# Wacky_Racers_87557913.net
KiCad netlist of a schematic drawn in Altium Designer
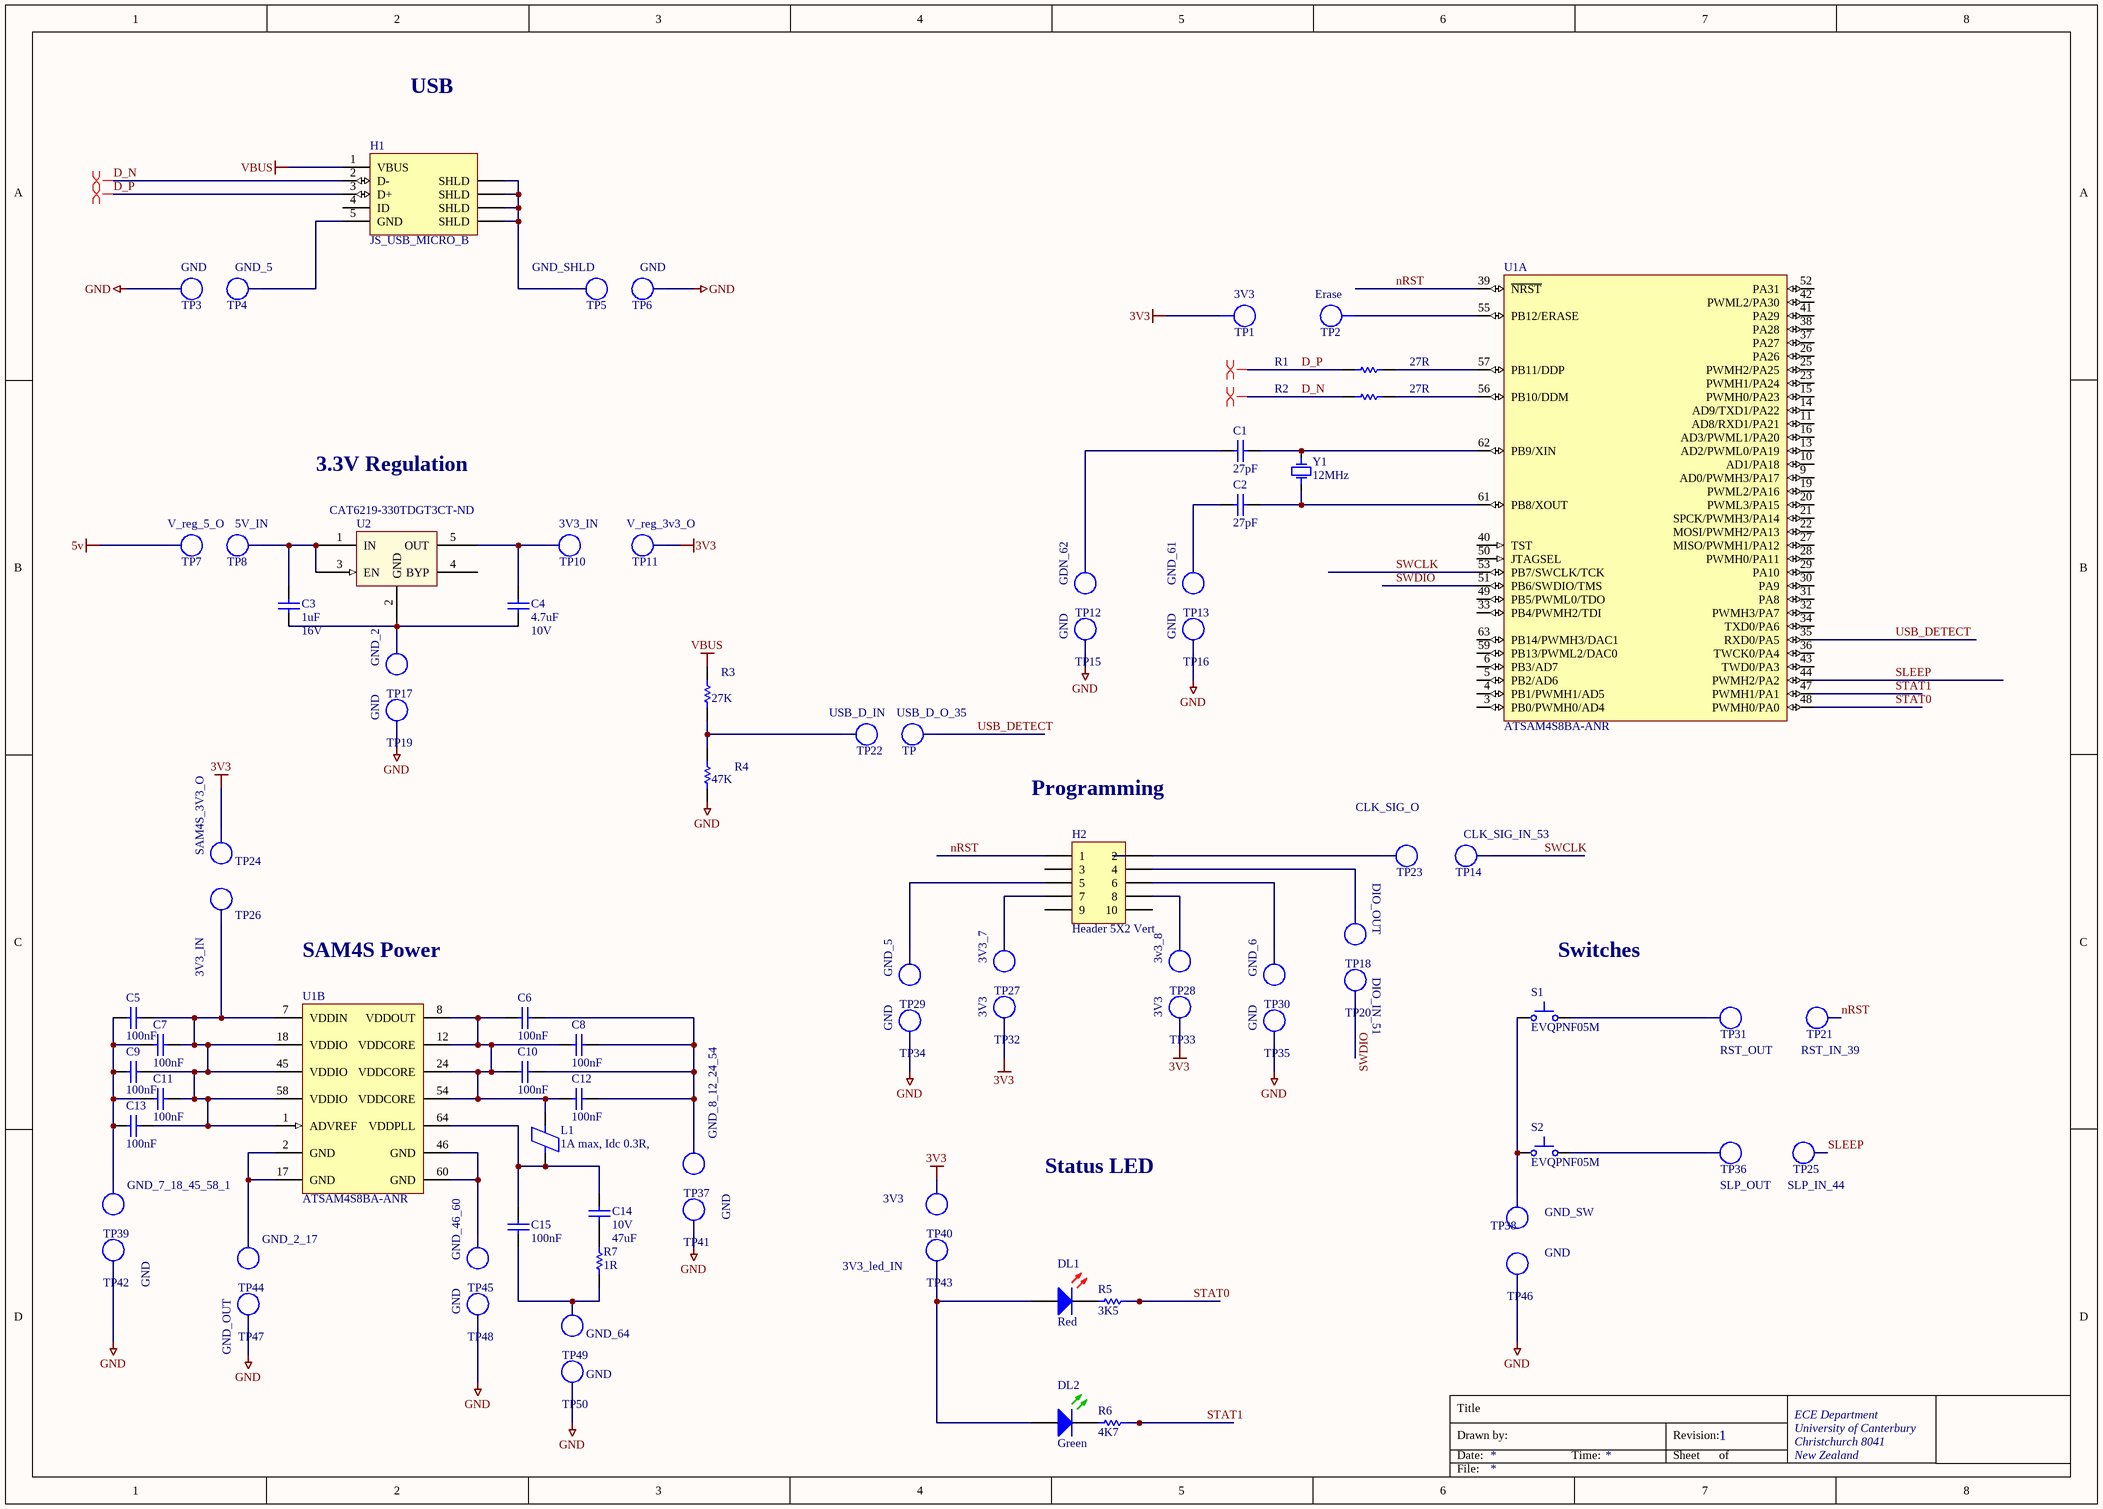
[diagram p0: Wacky_Racers_87557913.SchDoc]

(export (version "E")
  (design (tool "Eeschema 10.0.6"))
  (components
    (comp (ref "C1")
      (value "27pF")
      (footprint "CAPC1608L")
      (description "CAP CER 27pF NPO/COG +-5% 50V 0603")
      (libsource (lib "ECE AD19Components_22V1") (part "CC_27pF_0603"))
    )
    (comp (ref "C2")
      (value "27pF")
      (footprint "CAPC1608L")
      (description "CAP CER 27pF NPO/COG +-5% 50V 0603")
      (libsource (lib "ECE AD19Components_22V1") (part "CC_27pF_0603"))
    )
    (comp (ref "C3")
      (value "1uF")
      (footprint "CAPC1608L")
      (description "CAP CER 1uF Y5V -20% +80% 16V 0603")
      (fields (field (name "MAX VOLTAGE") "16V"))
      (libsource (lib "ECE AD19Components_22V1") (part "CC_1uF_0603"))
    )
    (comp (ref "C4")
      (value "4.7uF")
      (footprint "CAPC1608N")
      (description "CAP CER 4.7uF X5R +-20%  10V 0603")
      (fields (field (name "MAX VOLTAGE") "10V"))
      (libsource (lib "ECE AD19Components_22V1") (part "CC_4.7uF_0603"))
    )
    (comp (ref "C5")
      (value "100nF")
      (footprint "CAPC1608L")
      (description "CAP CER 100nF X7R +-10% 50V 0603")
      (libsource (lib "ECE AD19Components_22V1") (part "CC_100nF_0603"))
    )
    (comp (ref "C6")
      (value "100nF")
      (footprint "CAPC1608L")
      (description "CAP CER 100nF X7R +-10% 50V 0603")
      (libsource (lib "ECE AD19Components_22V1") (part "CC_100nF_0603"))
    )
    (comp (ref "C7")
      (value "100nF")
      (footprint "CAPC1608L")
      (description "CAP CER 100nF X7R +-10% 50V 0603")
      (libsource (lib "ECE AD19Components_22V1") (part "CC_100nF_0603"))
    )
    (comp (ref "C8")
      (value "100nF")
      (footprint "CAPC1608L")
      (description "CAP CER 100nF X7R +-10% 50V 0603")
      (libsource (lib "ECE AD19Components_22V1") (part "CC_100nF_0603"))
    )
    (comp (ref "C9")
      (value "100nF")
      (footprint "CAPC1608L")
      (description "CAP CER 100nF X7R +-10% 50V 0603")
      (libsource (lib "ECE AD19Components_22V1") (part "CC_100nF_0603"))
    )
    (comp (ref "C10")
      (value "100nF")
      (footprint "CAPC1608L")
      (description "CAP CER 100nF X7R +-10% 50V 0603")
      (libsource (lib "ECE AD19Components_22V1") (part "CC_100nF_0603"))
    )
    (comp (ref "C11")
      (value "100nF")
      (footprint "CAPC1608L")
      (description "CAP CER 100nF X7R +-10% 50V 0603")
      (libsource (lib "ECE AD19Components_22V1") (part "CC_100nF_0603"))
    )
    (comp (ref "C12")
      (value "100nF")
      (footprint "CAPC1608L")
      (description "CAP CER 100nF X7R +-10% 50V 0603")
      (libsource (lib "ECE AD19Components_22V1") (part "CC_100nF_0603"))
    )
    (comp (ref "C13")
      (value "100nF")
      (footprint "CAPC1608L")
      (description "CAP CER 100nF X7R +-10% 50V 0603")
      (libsource (lib "ECE AD19Components_22V1") (part "CC_100nF_0603"))
    )
    (comp (ref "C14")
      (value "47uF")
      (footprint "CAPC3216L")
      (description "CAP CER 47uF X5R -/+20% 10V 1206")
      (fields (field (name "MAX VOLTAGE") "10V"))
      (libsource (lib "ECE AD19Components_22V1") (part "CC_47uF_1206"))
    )
    (comp (ref "C15")
      (value "100nF")
      (footprint "CAPC1608L")
      (description "CAP CER 100nF X7R +-10% 50V 0603")
      (libsource (lib "ECE AD19Components_22V1") (part "CC_100nF_0603"))
    )
    (comp (ref "DL1")
      (value "Red")
      (footprint "WL-SMCW0603")
      (description "LED Red 250mcd 0603 SMD")
      (fields
        (field (name "MANUFACTURER") "WURTH ELEKTRONIK")
        (field (name "MANUFACTURER PART NUMBER") "150060RS75000")
        (field (name "LED COLOUR") "Red")
      )
      (libsource (lib "ECE AD19Components_22V1") (part "DL_150060RS75000"))
    )
    (comp (ref "DL2")
      (value "Green")
      (footprint "WL-SMCW0603")
      (description "LED Green 430mcd 0603 SMD")
      (fields
        (field (name "MANUFACTURER") "WURTH ELEKTRONIK")
        (field (name "MANUFACTURER PART NUMBER") "150060GS75000")
        (field (name "LED COLOUR") "Green")
      )
      (libsource (lib "ECE AD19Components_22V1") (part "DL_150060GS75000"))
    )
    (comp (ref "H1")
      (value "JS_USB_MICRO_B")
      (footprint "FCI_USB_10118194-0001LF")
      (description "CONN USB MICRO B RECPT SMT R/A")
      (fields (field (name "MANUFACTURER") "FCI") (field (name "MANUFACTURER PART NUMBER") "10118194-0001LF"))
      (libsource (lib "ECE AD19Components_22V1") (part "JS_USB_MICRO_B_SMT"))
    )
    (comp (ref "H2")
      (value "Header 5X2 Vert")
      (footprint "IDC2.54-V10D")
      (description "IDC Header, 2,54mm, 10-Pin, Vert")
      (libsource (lib "ECE AD19Components_22V1") (part "JA_HDR_IDC_5X2_VERT"))
    )
    (comp (ref "L1")
      (value "1A max, Idc 0.3R,")
      (footprint "INDC3216L")
      (description "Ferrite Bead, Rdc 0.3R, Z100MHZ 600R, Imax 1A, SMD 1206")
      (fields
        (field (name "MANUFACTURER") "FAIR-RITE")
        (field (name "MANUFACTURER PART NUMBER") "2512066017Y1")
      )
      (libsource (lib "ECE AD19Components_22V1") (part "IN_Ferrite-Bead"))
    )
    (comp (ref "R1")
      (value "27R")
      (footprint "RESC1608L")
      (description "RES 27 OHM 1/10W 5% 0603 SMD")
      (libsource (lib "ECE AD19Components_22V1") (part "RS_27R"))
    )
    (comp (ref "R2")
      (value "27R")
      (footprint "RESC1608L")
      (description "RES 27 OHM 1/10W 5% 0603 SMD")
      (libsource (lib "ECE AD19Components_22V1") (part "RS_27R"))
    )
    (comp (ref "R3")
      (value "27K")
      (footprint "RESC1608L")
      (description "RES 27K OHM 1/10W 5% 0603 SMD")
      (libsource (lib "ECE AD19Components_22V1") (part "RS_27K"))
    )
    (comp (ref "R4")
      (value "47K")
      (footprint "RESC1608N")
      (description "RES 47.0K OHM 1/10W 5% 0603 SMD")
      (libsource (lib "ECE AD19Components_22V1") (part "RS_47K"))
    )
    (comp (ref "R5")
      (value "3K5")
      (footprint "RESC1608L")
      (description "RES 4.7K OHM 1/10W 5% 0603 SMD")
      (libsource (lib "ECE AD19Components_22V1") (part "RS_4K7"))
    )
    (comp (ref "R6")
      (value "4K7")
      (footprint "RESC1608L")
      (description "RES 4.7K OHM 1/10W 5% 0603 SMD")
      (libsource (lib "ECE AD19Components_22V1") (part "RS_4K7"))
    )
    (comp (ref "R7")
      (value "1R")
      (footprint "RESC3216L")
      (description "RES 1R OHM 1/4W 5% 1206 SMD")
      (libsource (lib "ECE AD19Components_22V1") (part "RT_1R"))
    )
    (comp (ref "S1")
      (value "EVQPNF05M")
      (footprint "EVQPNF05M")
      (description "Panasonic 6 x 3.5mm SMD Light Touch Switch Type SMD")
      (fields (field (name "MANUFACTURER") "Panasonic"))
      (libsource (lib "ECE AD19Components_22V1") (part "WS_EVQPNF05M"))
    )
    (comp (ref "S2")
      (value "EVQPNF05M")
      (footprint "EVQPNF05M")
      (description "Panasonic 6 x 3.5mm SMD Light Touch Switch Type SMD")
      (fields (field (name "MANUFACTURER") "Panasonic"))
      (libsource (lib "ECE AD19Components_22V1") (part "WS_EVQPNF05M"))
    )
    (comp (ref "TP")
      (value "TP_0603")
      (footprint "TP_0603")
      (description "Test Point 1.65X0.9X1.2mm SMD")
      (fields
        (field (name "MANUFACTURER") "TE Connectivity AMP Connectors")
        (field (name "MANUFACTURER PART NUMBER") "1625854-3")
      )
      (libsource (lib "ECE AD19Components_22V1") (part "TP_0603"))
    )
    (comp (ref "TP1")
      (value "TP")
      (footprint "TP_1206")
      (description "Test-Point 3.3x1.6x2.1mm SMD")
      (fields
        (field (name "MANUFACTURER") "Harwin Inc")
        (field (name "MANUFACTURER PART NUMBER") "S1751-46R")
      )
      (libsource (lib "ECE AD19Components_22V1") (part "TP_1206"))
    )
    (comp (ref "TP2")
      (value "TP")
      (footprint "TP_1206")
      (description "Test-Point 3.3x1.6x2.1mm SMD")
      (fields
        (field (name "MANUFACTURER") "Harwin Inc")
        (field (name "MANUFACTURER PART NUMBER") "S1751-46R")
      )
      (libsource (lib "ECE AD19Components_22V1") (part "TP_1206"))
    )
    (comp (ref "TP3")
      (value "TP_0603")
      (footprint "TP_0603")
      (description "Test Point 1.65X0.9X1.2mm SMD")
      (fields
        (field (name "MANUFACTURER") "TE Connectivity AMP Connectors")
        (field (name "MANUFACTURER PART NUMBER") "1625854-3")
      )
      (libsource (lib "ECE AD19Components_22V1") (part "TP_0603"))
    )
    (comp (ref "TP4")
      (value "TP_0603")
      (footprint "TP_0603")
      (description "Test Point 1.65X0.9X1.2mm SMD")
      (fields
        (field (name "MANUFACTURER") "TE Connectivity AMP Connectors")
        (field (name "MANUFACTURER PART NUMBER") "1625854-3")
      )
      (libsource (lib "ECE AD19Components_22V1") (part "TP_0603"))
    )
    (comp (ref "TP5")
      (value "TP_0603")
      (footprint "TP_0603")
      (description "Test Point 1.65X0.9X1.2mm SMD")
      (fields
        (field (name "MANUFACTURER") "TE Connectivity AMP Connectors")
        (field (name "MANUFACTURER PART NUMBER") "1625854-3")
      )
      (libsource (lib "ECE AD19Components_22V1") (part "TP_0603"))
    )
    (comp (ref "TP6")
      (value "TP_0603")
      (footprint "TP_0603")
      (description "Test Point 1.65X0.9X1.2mm SMD")
      (fields
        (field (name "MANUFACTURER") "TE Connectivity AMP Connectors")
        (field (name "MANUFACTURER PART NUMBER") "1625854-3")
      )
      (libsource (lib "ECE AD19Components_22V1") (part "TP_0603"))
    )
    (comp (ref "TP7")
      (value "TP_0603")
      (footprint "TP_0603")
      (description "Test Point 1.65X0.9X1.2mm SMD")
      (fields
        (field (name "MANUFACTURER") "TE Connectivity AMP Connectors")
        (field (name "MANUFACTURER PART NUMBER") "1625854-3")
      )
      (libsource (lib "ECE AD19Components_22V1") (part "TP_0603"))
    )
    (comp (ref "TP8")
      (value "TP_0603")
      (footprint "TP_0603")
      (description "Test Point 1.65X0.9X1.2mm SMD")
      (fields
        (field (name "MANUFACTURER") "TE Connectivity AMP Connectors")
        (field (name "MANUFACTURER PART NUMBER") "1625854-3")
      )
      (libsource (lib "ECE AD19Components_22V1") (part "TP_0603"))
    )
    (comp (ref "TP10")
      (value "TP_0603")
      (footprint "TP_0603")
      (description "Test Point 1.65X0.9X1.2mm SMD")
      (fields
        (field (name "MANUFACTURER") "TE Connectivity AMP Connectors")
        (field (name "MANUFACTURER PART NUMBER") "1625854-3")
      )
      (libsource (lib "ECE AD19Components_22V1") (part "TP_0603"))
    )
    (comp (ref "TP11")
      (value "TP_0603")
      (footprint "TP_0603")
      (description "Test Point 1.65X0.9X1.2mm SMD")
      (fields
        (field (name "MANUFACTURER") "TE Connectivity AMP Connectors")
        (field (name "MANUFACTURER PART NUMBER") "1625854-3")
      )
      (libsource (lib "ECE AD19Components_22V1") (part "TP_0603"))
    )
    (comp (ref "TP12")
      (value "TP_0603")
      (footprint "TP_0603")
      (description "Test Point 1.65X0.9X1.2mm SMD")
      (fields
        (field (name "MANUFACTURER") "TE Connectivity AMP Connectors")
        (field (name "MANUFACTURER PART NUMBER") "1625854-3")
      )
      (libsource (lib "ECE AD19Components_22V1") (part "TP_0603"))
    )
    (comp (ref "TP13")
      (value "TP_0603")
      (footprint "TP_0603")
      (description "Test Point 1.65X0.9X1.2mm SMD")
      (fields
        (field (name "MANUFACTURER") "TE Connectivity AMP Connectors")
        (field (name "MANUFACTURER PART NUMBER") "1625854-3")
      )
      (libsource (lib "ECE AD19Components_22V1") (part "TP_0603"))
    )
    (comp (ref "TP14")
      (value "TP_0603")
      (footprint "TP_0603")
      (description "Test Point 1.65X0.9X1.2mm SMD")
      (fields
        (field (name "MANUFACTURER") "TE Connectivity AMP Connectors")
        (field (name "MANUFACTURER PART NUMBER") "1625854-3")
      )
      (libsource (lib "ECE AD19Components_22V1") (part "TP_0603"))
    )
    (comp (ref "TP15")
      (value "TP_0603")
      (footprint "TP_0603")
      (description "Test Point 1.65X0.9X1.2mm SMD")
      (fields
        (field (name "MANUFACTURER") "TE Connectivity AMP Connectors")
        (field (name "MANUFACTURER PART NUMBER") "1625854-3")
      )
      (libsource (lib "ECE AD19Components_22V1") (part "TP_0603"))
    )
    (comp (ref "TP16")
      (value "TP_0603")
      (footprint "TP_0603")
      (description "Test Point 1.65X0.9X1.2mm SMD")
      (fields
        (field (name "MANUFACTURER") "TE Connectivity AMP Connectors")
        (field (name "MANUFACTURER PART NUMBER") "1625854-3")
      )
      (libsource (lib "ECE AD19Components_22V1") (part "TP_0603"))
    )
    (comp (ref "TP17")
      (value "TP_0603")
      (footprint "TP_0603")
      (description "Test Point 1.65X0.9X1.2mm SMD")
      (fields
        (field (name "MANUFACTURER") "TE Connectivity AMP Connectors")
        (field (name "MANUFACTURER PART NUMBER") "1625854-3")
      )
      (libsource (lib "ECE AD19Components_22V1") (part "TP_0603"))
    )
    (comp (ref "TP18")
      (value "TP_0603")
      (footprint "TP_0603")
      (description "Test Point 1.65X0.9X1.2mm SMD")
      (fields
        (field (name "MANUFACTURER") "TE Connectivity AMP Connectors")
        (field (name "MANUFACTURER PART NUMBER") "1625854-3")
      )
      (libsource (lib "ECE AD19Components_22V1") (part "TP_0603"))
    )
    (comp (ref "TP19")
      (value "TP_0603")
      (footprint "TP_0603")
      (description "Test Point 1.65X0.9X1.2mm SMD")
      (fields
        (field (name "MANUFACTURER") "TE Connectivity AMP Connectors")
        (field (name "MANUFACTURER PART NUMBER") "1625854-3")
      )
      (libsource (lib "ECE AD19Components_22V1") (part "TP_0603"))
    )
    (comp (ref "TP20")
      (value "TP_0603")
      (footprint "TP_0603")
      (description "Test Point 1.65X0.9X1.2mm SMD")
      (fields
        (field (name "MANUFACTURER") "TE Connectivity AMP Connectors")
        (field (name "MANUFACTURER PART NUMBER") "1625854-3")
      )
      (libsource (lib "ECE AD19Components_22V1") (part "TP_0603"))
    )
    (comp (ref "TP21")
      (value "TP_0603")
      (footprint "TP_0603")
      (description "Test Point 1.65X0.9X1.2mm SMD")
      (fields
        (field (name "MANUFACTURER") "TE Connectivity AMP Connectors")
        (field (name "MANUFACTURER PART NUMBER") "1625854-3")
      )
      (libsource (lib "ECE AD19Components_22V1") (part "TP_0603"))
    )
    (comp (ref "TP22")
      (value "TP_0603")
      (footprint "TP_0603")
      (description "Test Point 1.65X0.9X1.2mm SMD")
      (fields
        (field (name "MANUFACTURER") "TE Connectivity AMP Connectors")
        (field (name "MANUFACTURER PART NUMBER") "1625854-3")
      )
      (libsource (lib "ECE AD19Components_22V1") (part "TP_0603"))
    )
    (comp (ref "TP23")
      (value "TP_0603")
      (footprint "TP_0603")
      (description "Test Point 1.65X0.9X1.2mm SMD")
      (fields
        (field (name "MANUFACTURER") "TE Connectivity AMP Connectors")
        (field (name "MANUFACTURER PART NUMBER") "1625854-3")
      )
      (libsource (lib "ECE AD19Components_22V1") (part "TP_0603"))
    )
    (comp (ref "TP24")
      (value "TP_0603")
      (footprint "TP_0603")
      (description "Test Point 1.65X0.9X1.2mm SMD")
      (fields
        (field (name "MANUFACTURER") "TE Connectivity AMP Connectors")
        (field (name "MANUFACTURER PART NUMBER") "1625854-3")
      )
      (libsource (lib "ECE AD19Components_22V1") (part "TP_0603"))
    )
    (comp (ref "TP25")
      (value "TP_0603")
      (footprint "TP_0603")
      (description "Test Point 1.65X0.9X1.2mm SMD")
      (fields
        (field (name "MANUFACTURER") "TE Connectivity AMP Connectors")
        (field (name "MANUFACTURER PART NUMBER") "1625854-3")
      )
      (libsource (lib "ECE AD19Components_22V1") (part "TP_0603"))
    )
    (comp (ref "TP26")
      (value "TP_0603")
      (footprint "TP_0603")
      (description "Test Point 1.65X0.9X1.2mm SMD")
      (fields
        (field (name "MANUFACTURER") "TE Connectivity AMP Connectors")
        (field (name "MANUFACTURER PART NUMBER") "1625854-3")
      )
      (libsource (lib "ECE AD19Components_22V1") (part "TP_0603"))
    )
    (comp (ref "TP27")
      (value "TP_0603")
      (footprint "TP_0603")
      (description "Test Point 1.65X0.9X1.2mm SMD")
      (fields
        (field (name "MANUFACTURER") "TE Connectivity AMP Connectors")
        (field (name "MANUFACTURER PART NUMBER") "1625854-3")
      )
      (libsource (lib "ECE AD19Components_22V1") (part "TP_0603"))
    )
    (comp (ref "TP28")
      (value "TP_0603")
      (footprint "TP_0603")
      (description "Test Point 1.65X0.9X1.2mm SMD")
      (fields
        (field (name "MANUFACTURER") "TE Connectivity AMP Connectors")
        (field (name "MANUFACTURER PART NUMBER") "1625854-3")
      )
      (libsource (lib "ECE AD19Components_22V1") (part "TP_0603"))
    )
    (comp (ref "TP29")
      (value "TP_0603")
      (footprint "TP_0603")
      (description "Test Point 1.65X0.9X1.2mm SMD")
      (fields
        (field (name "MANUFACTURER") "TE Connectivity AMP Connectors")
        (field (name "MANUFACTURER PART NUMBER") "1625854-3")
      )
      (libsource (lib "ECE AD19Components_22V1") (part "TP_0603"))
    )
    (comp (ref "TP30")
      (value "TP_0603")
      (footprint "TP_0603")
      (description "Test Point 1.65X0.9X1.2mm SMD")
      (fields
        (field (name "MANUFACTURER") "TE Connectivity AMP Connectors")
        (field (name "MANUFACTURER PART NUMBER") "1625854-3")
      )
      (libsource (lib "ECE AD19Components_22V1") (part "TP_0603"))
    )
    (comp (ref "TP31")
      (value "TP_0603")
      (footprint "TP_0603")
      (description "Test Point 1.65X0.9X1.2mm SMD")
      (fields
        (field (name "MANUFACTURER") "TE Connectivity AMP Connectors")
        (field (name "MANUFACTURER PART NUMBER") "1625854-3")
      )
      (libsource (lib "ECE AD19Components_22V1") (part "TP_0603"))
    )
    (comp (ref "TP32")
      (value "TP_0603")
      (footprint "TP_0603")
      (description "Test Point 1.65X0.9X1.2mm SMD")
      (fields
        (field (name "MANUFACTURER") "TE Connectivity AMP Connectors")
        (field (name "MANUFACTURER PART NUMBER") "1625854-3")
      )
      (libsource (lib "ECE AD19Components_22V1") (part "TP_0603"))
    )
    (comp (ref "TP33")
      (value "TP_0603")
      (footprint "TP_0603")
      (description "Test Point 1.65X0.9X1.2mm SMD")
      (fields
        (field (name "MANUFACTURER") "TE Connectivity AMP Connectors")
        (field (name "MANUFACTURER PART NUMBER") "1625854-3")
      )
      (libsource (lib "ECE AD19Components_22V1") (part "TP_0603"))
    )
    (comp (ref "TP34")
      (value "TP_0603")
      (footprint "TP_0603")
      (description "Test Point 1.65X0.9X1.2mm SMD")
      (fields
        (field (name "MANUFACTURER") "TE Connectivity AMP Connectors")
        (field (name "MANUFACTURER PART NUMBER") "1625854-3")
      )
      (libsource (lib "ECE AD19Components_22V1") (part "TP_0603"))
    )
    (comp (ref "TP35")
      (value "TP_0603")
      (footprint "TP_0603")
      (description "Test Point 1.65X0.9X1.2mm SMD")
      (fields
        (field (name "MANUFACTURER") "TE Connectivity AMP Connectors")
        (field (name "MANUFACTURER PART NUMBER") "1625854-3")
      )
      (libsource (lib "ECE AD19Components_22V1") (part "TP_0603"))
    )
    (comp (ref "TP36")
      (value "TP_0603")
      (footprint "TP_0603")
      (description "Test Point 1.65X0.9X1.2mm SMD")
      (fields
        (field (name "MANUFACTURER") "TE Connectivity AMP Connectors")
        (field (name "MANUFACTURER PART NUMBER") "1625854-3")
      )
      (libsource (lib "ECE AD19Components_22V1") (part "TP_0603"))
    )
    (comp (ref "TP37")
      (value "TP_0603")
      (footprint "TP_0603")
      (description "Test Point 1.65X0.9X1.2mm SMD")
      (fields
        (field (name "MANUFACTURER") "TE Connectivity AMP Connectors")
        (field (name "MANUFACTURER PART NUMBER") "1625854-3")
      )
      (libsource (lib "ECE AD19Components_22V1") (part "TP_0603"))
    )
    (comp (ref "TP38")
      (value "TP_0603")
      (footprint "TP_0603")
      (description "Test Point 1.65X0.9X1.2mm SMD")
      (fields
        (field (name "MANUFACTURER") "TE Connectivity AMP Connectors")
        (field (name "MANUFACTURER PART NUMBER") "1625854-3")
      )
      (libsource (lib "ECE AD19Components_22V1") (part "TP_0603"))
    )
    (comp (ref "TP39")
      (value "TP_0603")
      (footprint "TP_0603")
      (description "Test Point 1.65X0.9X1.2mm SMD")
      (fields
        (field (name "MANUFACTURER") "TE Connectivity AMP Connectors")
        (field (name "MANUFACTURER PART NUMBER") "1625854-3")
      )
      (libsource (lib "ECE AD19Components_22V1") (part "TP_0603"))
    )
    (comp (ref "TP40")
      (value "TP_0603")
      (footprint "TP_0603")
      (description "Test Point 1.65X0.9X1.2mm SMD")
      (fields
        (field (name "MANUFACTURER") "TE Connectivity AMP Connectors")
        (field (name "MANUFACTURER PART NUMBER") "1625854-3")
      )
      (libsource (lib "ECE AD19Components_22V1") (part "TP_0603"))
    )
    (comp (ref "TP41")
      (value "TP_0603")
      (footprint "TP_0603")
      (description "Test Point 1.65X0.9X1.2mm SMD")
      (fields
        (field (name "MANUFACTURER") "TE Connectivity AMP Connectors")
        (field (name "MANUFACTURER PART NUMBER") "1625854-3")
      )
      (libsource (lib "ECE AD19Components_22V1") (part "TP_0603"))
    )
    (comp (ref "TP42")
      (value "TP_0603")
      (footprint "TP_0603")
      (description "Test Point 1.65X0.9X1.2mm SMD")
      (fields
        (field (name "MANUFACTURER") "TE Connectivity AMP Connectors")
        (field (name "MANUFACTURER PART NUMBER") "1625854-3")
      )
      (libsource (lib "ECE AD19Components_22V1") (part "TP_0603"))
    )
    (comp (ref "TP43")
      (value "TP_0603")
      (footprint "TP_0603")
      (description "Test Point 1.65X0.9X1.2mm SMD")
      (fields
        (field (name "MANUFACTURER") "TE Connectivity AMP Connectors")
        (field (name "MANUFACTURER PART NUMBER") "1625854-3")
      )
      (libsource (lib "ECE AD19Components_22V1") (part "TP_0603"))
    )
    (comp (ref "TP44")
      (value "TP_0603")
      (footprint "TP_0603")
      (description "Test Point 1.65X0.9X1.2mm SMD")
      (fields
        (field (name "MANUFACTURER") "TE Connectivity AMP Connectors")
        (field (name "MANUFACTURER PART NUMBER") "1625854-3")
      )
      (libsource (lib "ECE AD19Components_22V1") (part "TP_0603"))
    )
    (comp (ref "TP45")
      (value "TP_0603")
      (footprint "TP_0603")
      (description "Test Point 1.65X0.9X1.2mm SMD")
      (fields
        (field (name "MANUFACTURER") "TE Connectivity AMP Connectors")
        (field (name "MANUFACTURER PART NUMBER") "1625854-3")
      )
      (libsource (lib "ECE AD19Components_22V1") (part "TP_0603"))
    )
    (comp (ref "TP46")
      (value "TP_0603")
      (footprint "TP_0603")
      (description "Test Point 1.65X0.9X1.2mm SMD")
      (fields
        (field (name "MANUFACTURER") "TE Connectivity AMP Connectors")
        (field (name "MANUFACTURER PART NUMBER") "1625854-3")
      )
      (libsource (lib "ECE AD19Components_22V1") (part "TP_0603"))
    )
    (comp (ref "TP47")
      (value "TP_0603")
      (footprint "TP_0603")
      (description "Test Point 1.65X0.9X1.2mm SMD")
      (fields
        (field (name "MANUFACTURER") "TE Connectivity AMP Connectors")
        (field (name "MANUFACTURER PART NUMBER") "1625854-3")
      )
      (libsource (lib "ECE AD19Components_22V1") (part "TP_0603"))
    )
    (comp (ref "TP48")
      (value "TP_0603")
      (footprint "TP_0603")
      (description "Test Point 1.65X0.9X1.2mm SMD")
      (fields
        (field (name "MANUFACTURER") "TE Connectivity AMP Connectors")
        (field (name "MANUFACTURER PART NUMBER") "1625854-3")
      )
      (libsource (lib "ECE AD19Components_22V1") (part "TP_0603"))
    )
    (comp (ref "TP49")
      (value "TP_0603")
      (footprint "TP_0603")
      (description "Test Point 1.65X0.9X1.2mm SMD")
      (fields
        (field (name "MANUFACTURER") "TE Connectivity AMP Connectors")
        (field (name "MANUFACTURER PART NUMBER") "1625854-3")
      )
      (libsource (lib "ECE AD19Components_22V1") (part "TP_0603"))
    )
    (comp (ref "TP50")
      (value "TP_0603")
      (footprint "TP_0603")
      (description "Test Point 1.65X0.9X1.2mm SMD")
      (fields
        (field (name "MANUFACTURER") "TE Connectivity AMP Connectors")
        (field (name "MANUFACTURER PART NUMBER") "1625854-3")
      )
      (libsource (lib "ECE AD19Components_22V1") (part "TP_0603"))
    )
    (comp (ref "U1")
      (value "ATSAM4S8BA-ANR")
      (footprint "LQFP64_L")
      (description "IC MCU 32BIT 512KB FLASH 64LQFP")
      (fields (field (name "MANUFACTURER") "Atmel"))
      (libsource (lib "ECE AD19Components_22V1") (part "SE_ATSAM4S16BA-MU"))
    )
    (comp (ref "U2")
      (value "CAT6219-330TDGT3")
      (footprint "SOT95P280X145-5N")
      (description "IC REG LIN 3.3V 500MA TSOT23-5")
      (fields
        (field (name "BASE PART NUMBER") "CAT6219")
        (field (name "SUPPLIER PART NUMBER") "CAT6219-330TDGT3CT-ND")
      )
      (libsource (lib "ENCE461AD19_V23") (part "SV_CAT6219-330TDGT3"))
    )
    (comp (ref "Y1")
      (value "12MHz")
      (footprint "6.0X3.5-4")
      (description "CRYSTAL 12MHZ 18PF 6X3.5mm SMD")
      (fields
        (field (name "MANUFACTURER") "CTS-Frequency Controls")
        (field (name "MANUFACTURER PART NUMBER") "406C35D12M00000")
        (field (name "FREQUENCY") "12MHz")
      )
      (libsource (lib "ECE AD19Components_22V1") (part "XT_CRYSTAL_12MHz_18pF"))
    )
  )
  (nets
    (net (code "1") (name "/D_N") (class "Default")
      (node (ref "H1") (pin "2") (pinfunction "D-_2") (pintype "bidirectional"))
      (node (ref "R2") (pin "1") (pinfunction "1_1") (pintype "passive"))
    )
    (net (code "2") (name "/D_P") (class "Default")
      (node (ref "H1") (pin "3") (pinfunction "D+_3") (pintype "bidirectional"))
      (node (ref "R1") (pin "1") (pinfunction "1_1") (pintype "passive"))
    )
    (net (code "3") (name "/SLEEP") (class "Default")
      (node (ref "TP25") (pin "1") (pinfunction "TP_1") (pintype "passive"))
      (node (ref "U1") (pin "44") (pinfunction "PWMH2/PA2_44") (pintype "bidirectional"))
    )
    (net (code "4") (name "/STAT0") (class "Default")
      (node (ref "R5") (pin "2") (pinfunction "2_2") (pintype "passive"))
      (node (ref "U1") (pin "48") (pinfunction "PWMH0/PA0_48") (pintype "bidirectional"))
    )
    (net (code "5") (name "/STAT1") (class "Default")
      (node (ref "R6") (pin "2") (pinfunction "2_2") (pintype "passive"))
      (node (ref "U1") (pin "47") (pinfunction "PWMH1/PA1_47") (pintype "bidirectional"))
    )
    (net (code "6") (name "/SWCLK") (class "Default")
      (node (ref "TP14") (pin "1") (pinfunction "TP_1") (pintype "passive"))
      (node (ref "U1") (pin "53") (pinfunction "PB7/SWCLK/TCK_53") (pintype "bidirectional"))
    )
    (net (code "7") (name "/SWDIO") (class "Default")
      (node (ref "TP20") (pin "1") (pinfunction "TP_1") (pintype "passive"))
      (node (ref "U1") (pin "51") (pinfunction "PB6/SWDIO/TMS_51") (pintype "bidirectional"))
    )
    (net (code "8") (name "/USB_DETECT") (class "Default")
      (node (ref "TP") (pin "1") (pinfunction "TP_1") (pintype "passive"))
      (node (ref "U1") (pin "35") (pinfunction "RXD0/PA5_35") (pintype "bidirectional"))
    )
    (net (code "9") (name "/nRST") (class "Default")
      (node (ref "H2") (pin "1") (pinfunction "1_1") (pintype "passive"))
      (node (ref "TP21") (pin "1") (pinfunction "TP_1") (pintype "passive"))
      (node (ref "U1") (pin "39") (pinfunction "~{NRST}_39") (pintype "bidirectional"))
    )
    (net (code "10") (name "3V3") (class "Default")
      (node (ref "TP1") (pin "1") (pinfunction "1_1") (pintype "passive"))
      (node (ref "TP11") (pin "1") (pinfunction "TP_1") (pintype "passive"))
      (node (ref "TP24") (pin "1") (pinfunction "TP_1") (pintype "passive"))
      (node (ref "TP32") (pin "1") (pinfunction "TP_1") (pintype "passive"))
      (node (ref "TP33") (pin "1") (pinfunction "TP_1") (pintype "passive"))
      (node (ref "TP40") (pin "1") (pinfunction "TP_1") (pintype "passive"))
    )
    (net (code "11") (name "5v") (class "Default")
      (node (ref "TP7") (pin "1") (pinfunction "TP_1") (pintype "passive"))
    )
    (net (code "12") (name "GND") (class "Default")
      (node (ref "R4") (pin "1") (pinfunction "1_1") (pintype "passive"))
      (node (ref "TP15") (pin "1") (pinfunction "TP_1") (pintype "passive"))
      (node (ref "TP16") (pin "1") (pinfunction "TP_1") (pintype "passive"))
      (node (ref "TP19") (pin "1") (pinfunction "TP_1") (pintype "passive"))
      (node (ref "TP3") (pin "1") (pinfunction "TP_1") (pintype "passive"))
      (node (ref "TP34") (pin "1") (pinfunction "TP_1") (pintype "passive"))
      (node (ref "TP35") (pin "1") (pinfunction "TP_1") (pintype "passive"))
      (node (ref "TP41") (pin "1") (pinfunction "TP_1") (pintype "passive"))
      (node (ref "TP42") (pin "1") (pinfunction "TP_1") (pintype "passive"))
      (node (ref "TP46") (pin "1") (pinfunction "TP_1") (pintype "passive"))
      (node (ref "TP47") (pin "1") (pinfunction "TP_1") (pintype "passive"))
      (node (ref "TP48") (pin "1") (pinfunction "TP_1") (pintype "passive"))
      (node (ref "TP50") (pin "1") (pinfunction "TP_1") (pintype "passive"))
      (node (ref "TP6") (pin "1") (pinfunction "TP_1") (pintype "passive"))
    )
    (net (code "13") (name "Net-(C14-Pad1)") (class "Default")
      (node (ref "C14") (pin "1") (pinfunction "1_1") (pintype "passive"))
      (node (ref "R7") (pin "2") (pinfunction "2_2") (pintype "passive"))
    )
    (net (code "14") (name "Net-(DL1-A)") (class "Default")
      (node (ref "DL1") (pin "2") (pinfunction "A_2") (pintype "passive"))
      (node (ref "DL2") (pin "2") (pinfunction "A_2") (pintype "passive"))
      (node (ref "TP43") (pin "1") (pinfunction "TP_1") (pintype "passive"))
    )
    (net (code "15") (name "Net-(H1-GND)") (class "Default")
      (node (ref "H1") (pin "5") (pinfunction "GND_5") (pintype "passive"))
      (node (ref "TP4") (pin "1") (pinfunction "TP_1") (pintype "passive"))
    )
    (net (code "16") (name "Net-(H1-SHLD)") (class "Default")
      (node (ref "H1") (pin "6") (pinfunction "SHLD_6") (pintype "passive"))
      (node (ref "TP5") (pin "1") (pinfunction "TP_1") (pintype "passive"))
    )
    (net (code "17") (name "Net-(TP8-TP)") (class "Default")
      (node (ref "C3") (pin "2") (pinfunction "2_2") (pintype "passive"))
      (node (ref "TP8") (pin "1") (pinfunction "TP_1") (pintype "passive"))
      (node (ref "U2") (pin "1") (pinfunction "IN_1") (pintype "power_in"))
      (node (ref "U2") (pin "3") (pinfunction "EN_3") (pintype "input"))
    )
    (net (code "18") (name "Net-(TP10-TP)") (class "Default")
      (node (ref "C4") (pin "2") (pinfunction "2_2") (pintype "passive"))
      (node (ref "TP10") (pin "1") (pinfunction "TP_1") (pintype "passive"))
      (node (ref "U2") (pin "5") (pinfunction "OUT_5") (pintype "power_in"))
    )
    (net (code "19") (name "Net-(TP12-TP)") (class "Default")
      (node (ref "C1") (pin "1") (pinfunction "1_1") (pintype "passive"))
      (node (ref "TP12") (pin "1") (pinfunction "TP_1") (pintype "passive"))
    )
    (net (code "20") (name "Net-(TP13-TP)") (class "Default")
      (node (ref "C2") (pin "1") (pinfunction "1_1") (pintype "passive"))
      (node (ref "TP13") (pin "1") (pinfunction "TP_1") (pintype "passive"))
    )
    (net (code "21") (name "Net-(TP17-TP)") (class "Default")
      (node (ref "C3") (pin "1") (pinfunction "1_1") (pintype "passive"))
      (node (ref "C4") (pin "1") (pinfunction "1_1") (pintype "passive"))
      (node (ref "TP17") (pin "1") (pinfunction "TP_1") (pintype "passive"))
      (node (ref "U2") (pin "2") (pinfunction "GND_2") (pintype "power_in"))
    )
    (net (code "22") (name "Net-(TP18-TP)") (class "Default")
      (node (ref "H2") (pin "4") (pinfunction "4_4") (pintype "passive"))
      (node (ref "TP18") (pin "1") (pinfunction "TP_1") (pintype "passive"))
    )
    (net (code "23") (name "Net-(TP22-TP)") (class "Default")
      (node (ref "R3") (pin "1") (pinfunction "1_1") (pintype "passive"))
      (node (ref "R4") (pin "2") (pinfunction "2_2") (pintype "passive"))
      (node (ref "TP22") (pin "1") (pinfunction "TP_1") (pintype "passive"))
    )
    (net (code "24") (name "Net-(TP23-TP)") (class "Default")
      (node (ref "H2") (pin "2") (pinfunction "2_2") (pintype "passive"))
      (node (ref "TP23") (pin "1") (pinfunction "TP_1") (pintype "passive"))
    )
    (net (code "25") (name "Net-(TP26-TP)") (class "Default")
      (node (ref "C11") (pin "2") (pinfunction "2_2") (pintype "passive"))
      (node (ref "C13") (pin "1") (pinfunction "1_1") (pintype "passive"))
      (node (ref "C5") (pin "2") (pinfunction "2_2") (pintype "passive"))
      (node (ref "C7") (pin "2") (pinfunction "2_2") (pintype "passive"))
      (node (ref "C9") (pin "2") (pinfunction "2_2") (pintype "passive"))
      (node (ref "TP26") (pin "1") (pinfunction "TP_1") (pintype "passive"))
      (node (ref "U1") (pin "1") (pinfunction "ADVREF_1") (pintype "input"))
      (node (ref "U1") (pin "18") (pinfunction "VDDIO_18") (pintype "power_in"))
      (node (ref "U1") (pin "45") (pinfunction "VDDIO_45") (pintype "power_in"))
      (node (ref "U1") (pin "58") (pinfunction "VDDIO_58") (pintype "power_in"))
      (node (ref "U1") (pin "7") (pinfunction "VDDIN_7") (pintype "power_in"))
    )
    (net (code "26") (name "Net-(TP27-TP)") (class "Default")
      (node (ref "H2") (pin "7") (pinfunction "7_7") (pintype "passive"))
      (node (ref "TP27") (pin "1") (pinfunction "TP_1") (pintype "passive"))
    )
    (net (code "27") (name "Net-(TP28-TP)") (class "Default")
      (node (ref "H2") (pin "8") (pinfunction "8_8") (pintype "passive"))
      (node (ref "TP28") (pin "1") (pinfunction "TP_1") (pintype "passive"))
    )
    (net (code "28") (name "Net-(TP29-TP)") (class "Default")
      (node (ref "H2") (pin "5") (pinfunction "5_5") (pintype "passive"))
      (node (ref "TP29") (pin "1") (pinfunction "TP_1") (pintype "passive"))
    )
    (net (code "29") (name "Net-(TP30-TP)") (class "Default")
      (node (ref "H2") (pin "6") (pinfunction "6_6") (pintype "passive"))
      (node (ref "TP30") (pin "1") (pinfunction "TP_1") (pintype "passive"))
    )
    (net (code "30") (name "Net-(TP31-TP)") (class "Default")
      (node (ref "S1") (pin "2") (pintype "passive"))
      (node (ref "TP31") (pin "1") (pinfunction "TP_1") (pintype "passive"))
    )
    (net (code "31") (name "Net-(TP36-TP)") (class "Default")
      (node (ref "S2") (pin "2") (pintype "passive"))
      (node (ref "TP36") (pin "1") (pinfunction "TP_1") (pintype "passive"))
    )
    (net (code "32") (name "Net-(TP37-TP)") (class "Default")
      (node (ref "C10") (pin "2") (pinfunction "2_2") (pintype "passive"))
      (node (ref "C12") (pin "2") (pinfunction "2_2") (pintype "passive"))
      (node (ref "C6") (pin "2") (pinfunction "2_2") (pintype "passive"))
      (node (ref "C8") (pin "2") (pinfunction "2_2") (pintype "passive"))
      (node (ref "TP37") (pin "1") (pinfunction "TP_1") (pintype "passive"))
    )
    (net (code "33") (name "Net-(TP38-TP)") (class "Default")
      (node (ref "S1") (pin "1") (pintype "passive"))
      (node (ref "S2") (pin "1") (pintype "passive"))
      (node (ref "TP38") (pin "1") (pinfunction "TP_1") (pintype "passive"))
    )
    (net (code "34") (name "Net-(TP39-TP)") (class "Default")
      (node (ref "C11") (pin "1") (pinfunction "1_1") (pintype "passive"))
      (node (ref "C13") (pin "2") (pinfunction "2_2") (pintype "passive"))
      (node (ref "C5") (pin "1") (pinfunction "1_1") (pintype "passive"))
      (node (ref "C7") (pin "1") (pinfunction "1_1") (pintype "passive"))
      (node (ref "C9") (pin "1") (pinfunction "1_1") (pintype "passive"))
      (node (ref "TP39") (pin "1") (pinfunction "TP_1") (pintype "passive"))
    )
    (net (code "35") (name "Net-(TP44-TP)") (class "Default")
      (node (ref "TP44") (pin "1") (pinfunction "TP_1") (pintype "passive"))
      (node (ref "U1") (pin "17") (pinfunction "GND_17") (pintype "power_in"))
      (node (ref "U1") (pin "2") (pinfunction "GND_2") (pintype "power_in"))
    )
    (net (code "36") (name "Net-(TP45-TP)") (class "Default")
      (node (ref "TP45") (pin "1") (pinfunction "TP_1") (pintype "passive"))
      (node (ref "U1") (pin "46") (pinfunction "GND_46") (pintype "power_in"))
      (node (ref "U1") (pin "60") (pinfunction "GND_60") (pintype "power_in"))
    )
    (net (code "37") (name "Net-(TP49-TP)") (class "Default")
      (node (ref "C15") (pin "1") (pinfunction "1_1") (pintype "passive"))
      (node (ref "R7") (pin "1") (pinfunction "1_1") (pintype "passive"))
      (node (ref "TP49") (pin "1") (pinfunction "TP_1") (pintype "passive"))
    )
    (net (code "38") (name "Net-(U1A-PB8{slash}XOUT)") (class "Default")
      (node (ref "C2") (pin "2") (pinfunction "2_2") (pintype "passive"))
      (node (ref "U1") (pin "61") (pinfunction "PB8/XOUT_61") (pintype "bidirectional"))
      (node (ref "Y1") (pin "1") (pinfunction "OSC1_1") (pintype "passive"))
    )
    (net (code "39") (name "Net-(U1A-PB9{slash}XIN)") (class "Default")
      (node (ref "C1") (pin "2") (pinfunction "2_2") (pintype "passive"))
      (node (ref "U1") (pin "62") (pinfunction "PB9/XIN_62") (pintype "bidirectional"))
      (node (ref "Y1") (pin "3") (pinfunction "OSC2_3") (pintype "passive"))
    )
    (net (code "40") (name "Net-(U1A-PB10{slash}DDM)") (class "Default")
      (node (ref "R2") (pin "2") (pinfunction "2_2") (pintype "passive"))
      (node (ref "U1") (pin "56") (pinfunction "PB10/DDM_56") (pintype "bidirectional"))
    )
    (net (code "41") (name "Net-(U1A-PB11{slash}DDP)") (class "Default")
      (node (ref "R1") (pin "2") (pinfunction "2_2") (pintype "passive"))
      (node (ref "U1") (pin "57") (pinfunction "PB11/DDP_57") (pintype "bidirectional"))
    )
    (net (code "42") (name "Net-(U1A-PB12{slash}ERASE)") (class "Default")
      (node (ref "TP2") (pin "1") (pinfunction "1_1") (pintype "passive"))
      (node (ref "U1") (pin "55") (pinfunction "PB12/ERASE_55") (pintype "bidirectional"))
    )
    (net (code "43") (name "Net-(U1B-VDDOUT)") (class "Default")
      (node (ref "C10") (pin "1") (pinfunction "1_1") (pintype "passive"))
      (node (ref "C12") (pin "1") (pinfunction "1_1") (pintype "passive"))
      (node (ref "C6") (pin "1") (pinfunction "1_1") (pintype "passive"))
      (node (ref "C8") (pin "1") (pinfunction "1_1") (pintype "passive"))
      (node (ref "L1") (pin "2") (pinfunction "2_2") (pintype "passive"))
      (node (ref "U1") (pin "12") (pinfunction "VDDCORE_12") (pintype "power_in"))
      (node (ref "U1") (pin "24") (pinfunction "VDDCORE_24") (pintype "power_in"))
      (node (ref "U1") (pin "54") (pinfunction "VDDCORE_54") (pintype "power_in"))
      (node (ref "U1") (pin "8") (pinfunction "VDDOUT_8") (pintype "power_in"))
    )
    (net (code "44") (name "Net-(U1B-VDDPLL)") (class "Default")
      (node (ref "C14") (pin "2") (pinfunction "2_2") (pintype "passive"))
      (node (ref "C15") (pin "2") (pinfunction "2_2") (pintype "passive"))
      (node (ref "L1") (pin "1") (pinfunction "1_1") (pintype "passive"))
      (node (ref "U1") (pin "64") (pinfunction "VDDPLL_64") (pintype "power_in"))
    )
    (net (code "45") (name "VBUS") (class "Default")
      (node (ref "H1") (pin "1") (pinfunction "VBUS_1") (pintype "power_in"))
      (node (ref "R3") (pin "2") (pinfunction "2_2") (pintype "passive"))
    )
    (net (code "46") (name "unconnected-(DL1-K-Pad1)") (class "Default")
      (node (ref "DL1") (pin "1") (pinfunction "K_1") (pintype "passive"))
    )
    (net (code "47") (name "unconnected-(DL2-K-Pad1)") (class "Default")
      (node (ref "DL2") (pin "1") (pinfunction "K_1") (pintype "passive"))
    )
    (net (code "48") (name "unconnected-(H1-ID-Pad4)") (class "Default")
      (node (ref "H1") (pin "4") (pinfunction "ID_4") (pintype "power_in"))
    )
    (net (code "49") (name "unconnected-(H2-Pad3)") (class "Default")
      (node (ref "H2") (pin "3") (pinfunction "3_3") (pintype "passive"))
    )
    (net (code "50") (name "unconnected-(H2-Pad9)") (class "Default")
      (node (ref "H2") (pin "9") (pinfunction "9_9") (pintype "passive"))
    )
    (net (code "51") (name "unconnected-(H2-Pad10)") (class "Default")
      (node (ref "H2") (pin "10") (pinfunction "10_10") (pintype "passive"))
    )
    (net (code "52") (name "unconnected-(R5-Pad1)") (class "Default")
      (node (ref "R5") (pin "1") (pinfunction "1_1") (pintype "passive"))
    )
    (net (code "53") (name "unconnected-(R6-Pad1)") (class "Default")
      (node (ref "R6") (pin "1") (pinfunction "1_1") (pintype "passive"))
    )
    (net (code "54") (name "unconnected-(U1A-AD0{slash}PWMH3{slash}PA17-Pad9)") (class "Default")
      (node (ref "U1") (pin "9") (pinfunction "AD0/PWMH3/PA17_9") (pintype "bidirectional"))
    )
    (net (code "55") (name "unconnected-(U1A-AD1{slash}PA18-Pad10)") (class "Default")
      (node (ref "U1") (pin "10") (pinfunction "AD1/PA18_10") (pintype "bidirectional"))
    )
    (net (code "56") (name "unconnected-(U1A-AD2{slash}PWML0{slash}PA19-Pad13)") (class "Default")
      (node (ref "U1") (pin "13") (pinfunction "AD2/PWML0/PA19_13") (pintype "bidirectional"))
    )
    (net (code "57") (name "unconnected-(U1A-AD3{slash}PWML1{slash}PA20-Pad16)") (class "Default")
      (node (ref "U1") (pin "16") (pinfunction "AD3/PWML1/PA20_16") (pintype "bidirectional"))
    )
    (net (code "58") (name "unconnected-(U1A-AD8{slash}RXD1{slash}PA21-Pad11)") (class "Default")
      (node (ref "U1") (pin "11") (pinfunction "AD8/RXD1/PA21_11") (pintype "bidirectional"))
    )
    (net (code "59") (name "unconnected-(U1A-AD9{slash}TXD1{slash}PA22-Pad14)") (class "Default")
      (node (ref "U1") (pin "14") (pinfunction "AD9/TXD1/PA22_14") (pintype "bidirectional"))
    )
    (net (code "60") (name "unconnected-(U1A-JTAGSEL-Pad50)") (class "Default")
      (node (ref "U1") (pin "50") (pinfunction "JTAGSEL_50") (pintype "input"))
    )
    (net (code "61") (name "unconnected-(U1A-MISO{slash}PWMH1{slash}PA12-Pad27)") (class "Default")
      (node (ref "U1") (pin "27") (pinfunction "MISO/PWMH1/PA12_27") (pintype "bidirectional"))
    )
    (net (code "62") (name "unconnected-(U1A-MOSI{slash}PWMH2{slash}PA13-Pad22)") (class "Default")
      (node (ref "U1") (pin "22") (pinfunction "MOSI/PWMH2/PA13_22") (pintype "bidirectional"))
    )
    (net (code "63") (name "unconnected-(U1A-PA8-Pad31)") (class "Default")
      (node (ref "U1") (pin "31") (pinfunction "PA8_31") (pintype "bidirectional"))
    )
    (net (code "64") (name "unconnected-(U1A-PA9-Pad30)") (class "Default")
      (node (ref "U1") (pin "30") (pinfunction "PA9_30") (pintype "bidirectional"))
    )
    (net (code "65") (name "unconnected-(U1A-PA10-Pad29)") (class "Default")
      (node (ref "U1") (pin "29") (pinfunction "PA10_29") (pintype "bidirectional"))
    )
    (net (code "66") (name "unconnected-(U1A-PA26-Pad26)") (class "Default")
      (node (ref "U1") (pin "26") (pinfunction "PA26_26") (pintype "bidirectional"))
    )
    (net (code "67") (name "unconnected-(U1A-PA27-Pad37)") (class "Default")
      (node (ref "U1") (pin "37") (pinfunction "PA27_37") (pintype "bidirectional"))
    )
    (net (code "68") (name "unconnected-(U1A-PA28-Pad38)") (class "Default")
      (node (ref "U1") (pin "38") (pinfunction "PA28_38") (pintype "bidirectional"))
    )
    (net (code "69") (name "unconnected-(U1A-PA29-Pad41)") (class "Default")
      (node (ref "U1") (pin "41") (pinfunction "PA29_41") (pintype "bidirectional"))
    )
    (net (code "70") (name "unconnected-(U1A-PA31-Pad52)") (class "Default")
      (node (ref "U1") (pin "52") (pinfunction "PA31_52") (pintype "bidirectional"))
    )
    (net (code "71") (name "unconnected-(U1A-PB0{slash}PWMH0{slash}AD4-Pad3)") (class "Default")
      (node (ref "U1") (pin "3") (pinfunction "PB0/PWMH0/AD4_3") (pintype "bidirectional"))
    )
    (net (code "72") (name "unconnected-(U1A-PB1{slash}PWMH1{slash}AD5-Pad4)") (class "Default")
      (node (ref "U1") (pin "4") (pinfunction "PB1/PWMH1/AD5_4") (pintype "bidirectional"))
    )
    (net (code "73") (name "unconnected-(U1A-PB2{slash}AD6-Pad5)") (class "Default")
      (node (ref "U1") (pin "5") (pinfunction "PB2/AD6_5") (pintype "bidirectional"))
    )
    (net (code "74") (name "unconnected-(U1A-PB3{slash}AD7-Pad6)") (class "Default")
      (node (ref "U1") (pin "6") (pinfunction "PB3/AD7_6") (pintype "bidirectional"))
    )
    (net (code "75") (name "unconnected-(U1A-PB4{slash}PWMH2{slash}TDI-Pad33)") (class "Default")
      (node (ref "U1") (pin "33") (pinfunction "PB4/PWMH2/TDI_33") (pintype "bidirectional"))
    )
    (net (code "76") (name "unconnected-(U1A-PB5{slash}PWML0{slash}TDO-Pad49)") (class "Default")
      (node (ref "U1") (pin "49") (pinfunction "PB5/PWML0/TDO_49") (pintype "bidirectional"))
    )
    (net (code "77") (name "unconnected-(U1A-PB13{slash}PWML2{slash}DAC0-Pad59)") (class "Default")
      (node (ref "U1") (pin "59") (pinfunction "PB13/PWML2/DAC0_59") (pintype "bidirectional"))
    )
    (net (code "78") (name "unconnected-(U1A-PB14{slash}PWMH3{slash}DAC1-Pad63)") (class "Default")
      (node (ref "U1") (pin "63") (pinfunction "PB14/PWMH3/DAC1_63") (pintype "bidirectional"))
    )
    (net (code "79") (name "unconnected-(U1A-PWMH0{slash}PA11-Pad28)") (class "Default")
      (node (ref "U1") (pin "28") (pinfunction "PWMH0/PA11_28") (pintype "bidirectional"))
    )
    (net (code "80") (name "unconnected-(U1A-PWMH0{slash}PA23-Pad15)") (class "Default")
      (node (ref "U1") (pin "15") (pinfunction "PWMH0/PA23_15") (pintype "bidirectional"))
    )
    (net (code "81") (name "unconnected-(U1A-PWMH1{slash}PA24-Pad23)") (class "Default")
      (node (ref "U1") (pin "23") (pinfunction "PWMH1/PA24_23") (pintype "bidirectional"))
    )
    (net (code "82") (name "unconnected-(U1A-PWMH2{slash}PA25-Pad25)") (class "Default")
      (node (ref "U1") (pin "25") (pinfunction "PWMH2/PA25_25") (pintype "bidirectional"))
    )
    (net (code "83") (name "unconnected-(U1A-PWMH3{slash}PA7-Pad32)") (class "Default")
      (node (ref "U1") (pin "32") (pinfunction "PWMH3/PA7_32") (pintype "bidirectional"))
    )
    (net (code "84") (name "unconnected-(U1A-PWML2{slash}PA16-Pad19)") (class "Default")
      (node (ref "U1") (pin "19") (pinfunction "PWML2/PA16_19") (pintype "bidirectional"))
    )
    (net (code "85") (name "unconnected-(U1A-PWML2{slash}PA30-Pad42)") (class "Default")
      (node (ref "U1") (pin "42") (pinfunction "PWML2/PA30_42") (pintype "bidirectional"))
    )
    (net (code "86") (name "unconnected-(U1A-PWML3{slash}PA15-Pad20)") (class "Default")
      (node (ref "U1") (pin "20") (pinfunction "PWML3/PA15_20") (pintype "bidirectional"))
    )
    (net (code "87") (name "unconnected-(U1A-SPCK{slash}PWMH3{slash}PA14-Pad21)") (class "Default")
      (node (ref "U1") (pin "21") (pinfunction "SPCK/PWMH3/PA14_21") (pintype "bidirectional"))
    )
    (net (code "88") (name "unconnected-(U1A-TST-Pad40)") (class "Default")
      (node (ref "U1") (pin "40") (pinfunction "TST_40") (pintype "input"))
    )
    (net (code "89") (name "unconnected-(U1A-TWCK0{slash}PA4-Pad36)") (class "Default")
      (node (ref "U1") (pin "36") (pinfunction "TWCK0/PA4_36") (pintype "bidirectional"))
    )
    (net (code "90") (name "unconnected-(U1A-TWD0{slash}PA3-Pad43)") (class "Default")
      (node (ref "U1") (pin "43") (pinfunction "TWD0/PA3_43") (pintype "bidirectional"))
    )
    (net (code "91") (name "unconnected-(U1A-TXD0{slash}PA6-Pad34)") (class "Default")
      (node (ref "U1") (pin "34") (pinfunction "TXD0/PA6_34") (pintype "bidirectional"))
    )
    (net (code "92") (name "unconnected-(U2-BYP-Pad4)") (class "Default")
      (node (ref "U2") (pin "4") (pinfunction "BYP_4") (pintype "passive"))
    )
  )
)
